# Power.net
KiCad netlist of a schematic drawn in Altium Designer
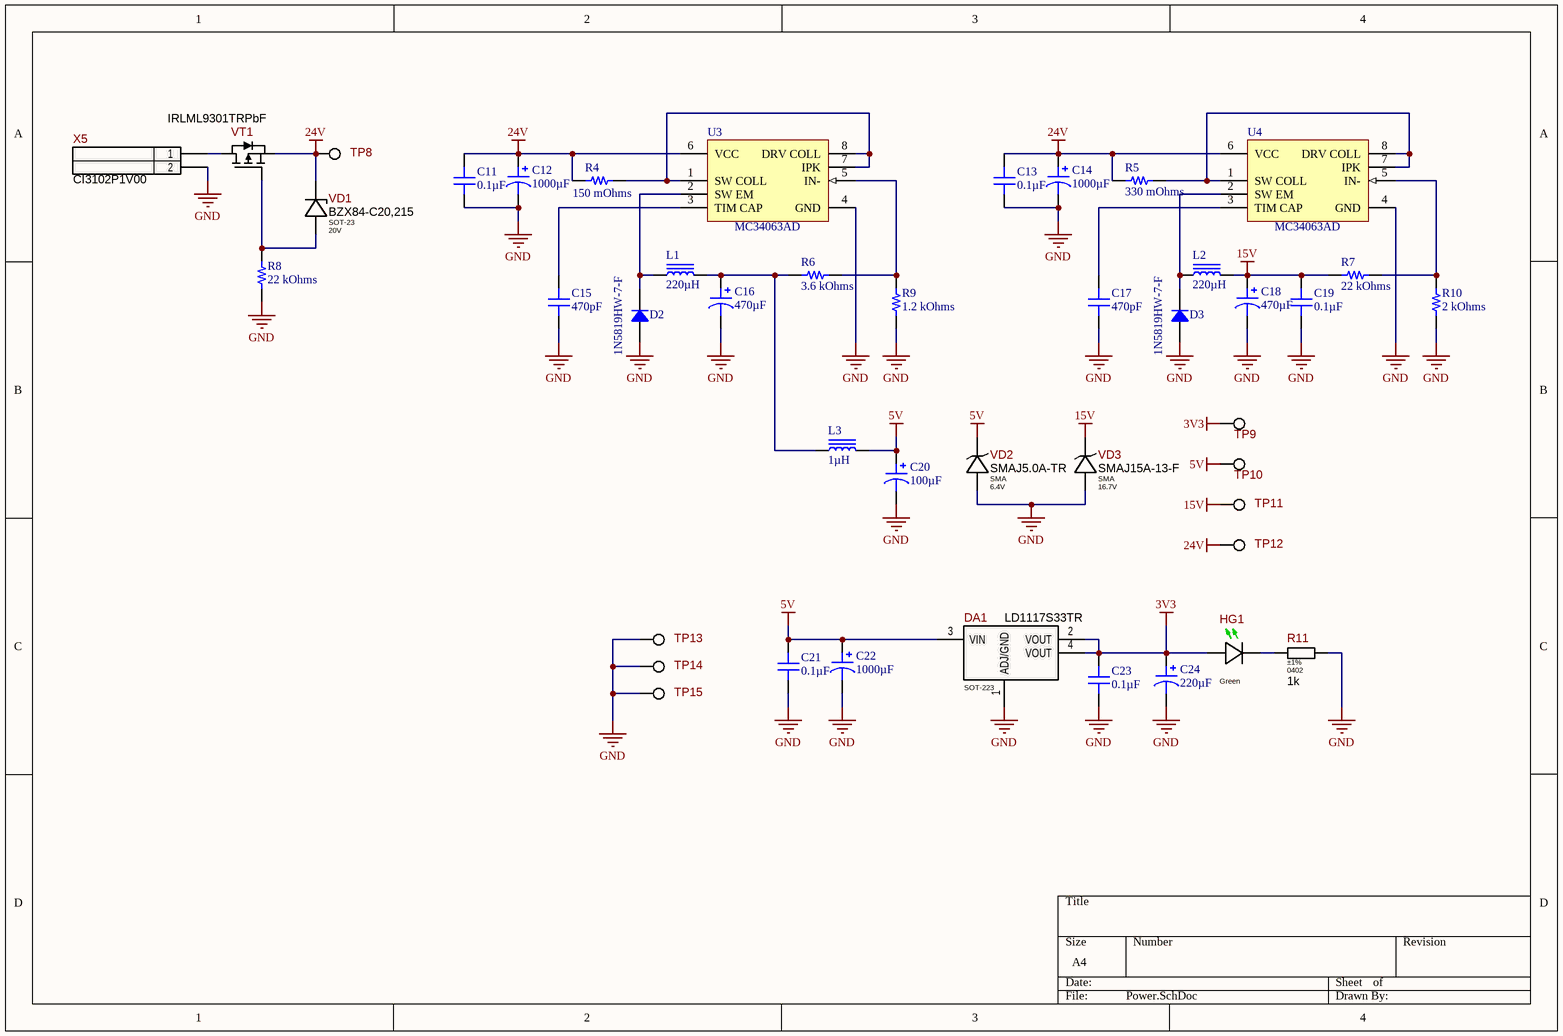
[diagram p0: Power.SchDoc]

(export (version "E")
  (design (tool "Eeschema 10.0.6"))
  (components
    (comp (ref "C11")
      (value "0.1µF")
      (footprint "CAP 0805_2012")
      (description "CAP CER 0.1UF 50V X7R 0805")
      (fields (field (name "PART NUMBER") "CC0805MRX7R9BB104") (field (name "MANUFACTURER") "Yageo"))
      (libsource (lib "Celestial Altium Library - altium_library") (part "Capacitor"))
    )
    (comp (ref "C12")
      (value "1000µF")
      (footprint "CAP TH ALUM ELEC D22.00mm S10.00mm H27.00mm")
      (description "CAP ALUM 1000UF 20% 35V SNAP IN")
      (fields (field (name "PART NUMBER") "LKG1V102MESZCK") (field (name "MANUFACTURER") "Nichicon"))
      (libsource (lib "Celestial Altium Library - altium_library") (part "Polarised Capacitor"))
    )
    (comp (ref "C13")
      (value "0.1µF")
      (footprint "CAP 0805_2012")
      (description "CAP CER 0.1UF 50V X7R 0805")
      (fields (field (name "PART NUMBER") "CC0805MRX7R9BB104") (field (name "MANUFACTURER") "Yageo"))
      (libsource (lib "Celestial Altium Library - altium_library") (part "Capacitor"))
    )
    (comp (ref "C14")
      (value "1000µF")
      (footprint "CAP TH ALUM ELEC D22.00mm S10.00mm H27.00mm")
      (description "CAP ALUM 1000UF 20% 35V SNAP IN")
      (fields (field (name "PART NUMBER") "LKG1V102MESZCK") (field (name "MANUFACTURER") "Nichicon"))
      (libsource (lib "Celestial Altium Library - altium_library") (part "Polarised Capacitor"))
    )
    (comp (ref "C15")
      (value "470pF")
      (footprint "CAP 0805_2012")
      (description "CAP CER 0805 470PF 50V ULTRA STA")
      (fields (field (name "PART NUMBER") "C0805X471J5HACAUTO") (field (name "MANUFACTURER") "KEMET"))
      (libsource (lib "Celestial Altium Library - altium_library") (part "Capacitor"))
    )
    (comp (ref "C16")
      (value "470µF")
      (footprint "CAP TH ALUM ELEC D8.00mm S3.50mm H12.50mm")
      (description "CAP ALUM 470UF 20% 10V RADIAL")
      (fields
        (field (name "PART NUMBER") "ECA-1AHG471")
        (field (name "MANUFACTURER") "Panasonic Electronic Components")
      )
      (libsource (lib "Celestial Altium Library - altium_library") (part "Polarised Capacitor"))
    )
    (comp (ref "C17")
      (value "470pF")
      (footprint "CAP 0805_2012")
      (description "CAP CER 0805 470PF 50V ULTRA STA")
      (fields (field (name "PART NUMBER") "C0805X471J5HACAUTO") (field (name "MANUFACTURER") "KEMET"))
      (libsource (lib "Celestial Altium Library - altium_library") (part "Capacitor"))
    )
    (comp (ref "C18")
      (value "470µF")
      (footprint "CAP TH ALUM ELEC D8.00mm S3.50mm H12.50mm")
      (description "CAP ALUM 470UF 20% 10V RADIAL")
      (fields
        (field (name "PART NUMBER") "ECA-1AHG471")
        (field (name "MANUFACTURER") "Panasonic Electronic Components")
      )
      (libsource (lib "Celestial Altium Library - altium_library") (part "Polarised Capacitor"))
    )
    (comp (ref "C19")
      (value "0.1µF")
      (footprint "CAP 0805_2012")
      (description "CAP CER 0.1UF 50V X7R 0805")
      (fields (field (name "PART NUMBER") "CC0805MRX7R9BB104") (field (name "MANUFACTURER") "Yageo"))
      (libsource (lib "Celestial Altium Library - altium_library") (part "Capacitor"))
    )
    (comp (ref "C20")
      (value "100µF")
      (footprint "CAP ALSMD 5.3MM H5.4MM")
      (description "CAP 100 UF 20% 6.3 V")
      (fields (field (name "PART NUMBER") "865090142005") (field (name "MANUFACTURER") "Würth Elektronik"))
      (libsource (lib "Celestial Altium Library - altium_library") (part "Polarised Capacitor"))
    )
    (comp (ref "C21")
      (value "0.1µF")
      (footprint "CAP 0805_2012")
      (description "CAP CER 0.1UF 50V X7R 0805")
      (fields (field (name "PART NUMBER") "CC0805MRX7R9BB104") (field (name "MANUFACTURER") "Yageo"))
      (libsource (lib "Celestial Altium Library - altium_library") (part "Capacitor"))
    )
    (comp (ref "C22")
      (value "1000µF")
      (footprint "CAP TH ALUM ELEC D22.00mm S10.00mm H27.00mm")
      (description "CAP ALUM 1000UF 20% 35V SNAP IN")
      (fields (field (name "PART NUMBER") "LKG1V102MESZCK") (field (name "MANUFACTURER") "Nichicon"))
      (libsource (lib "Celestial Altium Library - altium_library") (part "Polarised Capacitor"))
    )
    (comp (ref "C23")
      (value "0.1µF")
      (footprint "CAP 0805_2012")
      (description "CAP CER 0.1UF 50V X7R 0805")
      (fields (field (name "PART NUMBER") "CC0805MRX7R9BB104") (field (name "MANUFACTURER") "Yageo"))
      (libsource (lib "Celestial Altium Library - altium_library") (part "Capacitor"))
    )
    (comp (ref "C24")
      (value "220µF")
      (footprint "CAP ALSMD POLY 5.3MM H6.0MM")
      (description "CAP ALUM POLY 220UF 20% 6.3V SMD")
      (fields
        (field (name "PART NUMBER") "6SVPE220MW")
        (field (name "MANUFACTURER") "Panasonic Electronic Components")
      )
      (libsource (lib "Celestial Altium Library - altium_library") (part "Polarised Capacitor"))
    )
    (comp (ref "D2")
      (value "1N5819HW-7-F")
      (footprint "SOD-123")
      (description "DIODE SCHOTTKY 40V 1A SOD123")
      (fields (field (name "MANUFACTURER") "Diodes Incorporated"))
      (libsource (lib "Celestial Altium Library - altium_library") (part "Diode"))
    )
    (comp (ref "D3")
      (value "1N5819HW-7-F")
      (footprint "SOD-123")
      (description "DIODE SCHOTTKY 40V 1A SOD123")
      (fields (field (name "MANUFACTURER") "Diodes Incorporated"))
      (libsource (lib "Celestial Altium Library - altium_library") (part "Diode"))
    )
    (comp (ref "DA1")
      (value "LD1117S33TR")
      (footprint "SOT-223")
      (description "Adjustable and fixed low drop positive voltage regulator, 3.3V 800mA")
      (fields
        (field (name "PACKAGE") "SOT-223")
        (field (name "PART NUMBER") "LD1117S33TR")
        (field (name "MANUFACTURER") "STMicroelectronics")
      )
      (libsource (lib "SOG.T01.PWR.621.v1_1") (part "LD1117S33TR"))
    )
    (comp (ref "HG1")
      (value "19-21/GHC-YR1S2/3T")
      (footprint "LED-0603G-0.8mm")
      (description "Indication LED, Green 528nm, Clear, SMD 0603, Vf 2.7-3.7V, 112 - 285mcd @ 20mA, 110°")
      (fields (field (name "COLOR") "Green") (field (name "MANUFACTURER") "Everlight Electronics Co.,Ltd"))
      (libsource (lib "SOG.T01.PWR.621.v1_1") (part "19-21/GHC-YR1S2/3T"))
    )
    (comp (ref "L1")
      (value "220µH")
      (footprint "BOURNS SRR1280")
      (description "FIXED IND 220UH 1.6A 400MOHM SMD")
      (fields (field (name "PART NUMBER") "SRR1280-221K") (field (name "MANUFACTURER") "Bourns Inc."))
      (libsource (lib "Celestial Altium Library - altium_library") (part "Inductor"))
    )
    (comp (ref "L2")
      (value "220µH")
      (footprint "BOURNS SRR1280")
      (description "FIXED IND 220UH 1.6A 400MOHM SMD")
      (fields (field (name "PART NUMBER") "SRR1280-221K") (field (name "MANUFACTURER") "Bourns Inc."))
      (libsource (lib "Celestial Altium Library - altium_library") (part "Inductor"))
    )
    (comp (ref "L3")
      (value "1µH")
      (footprint "TAIYO YUDEN NRS5030")
      (description "FIXED IND 1UH 4A 19.5 MOHM SMD")
      (fields (field (name "PART NUMBER") "NRS5030T1R0NMGJV") (field (name "MANUFACTURER") "Taiyo Yuden"))
      (libsource (lib "Celestial Altium Library - altium_library") (part "Inductor"))
    )
    (comp (ref "R4")
      (value "150 mOhms")
      (footprint "RES 1206_3216")
      (description "RES 0.15 OHM 1% 1/4W 1206")
      (fields (field (name "PART NUMBER") "WSL1206R1500FEA") (field (name "MANUFACTURER") "Vishay Dale"))
      (libsource (lib "Celestial Altium Library - altium_library") (part "Resistor"))
    )
    (comp (ref "R5")
      (value "330 mOhms")
      (footprint "RES 1206_3216")
      (description "RES 0.33 OHM 1% 1/4W 1206")
      (fields
        (field (name "PART NUMBER") "ERJ-8RQFR33V")
        (field (name "MANUFACTURER") "Panasonic Electronic Components")
      )
      (libsource (lib "Celestial Altium Library - altium_library") (part "Resistor"))
    )
    (comp (ref "R6")
      (value "3.6 kOhms")
      (footprint "RES 0805_2012")
      (description "RES 3.6K OHM 1% 1/8W 0805")
      (fields
        (field (name "PART NUMBER") "RMCF0805FT3K60")
        (field (name "MANUFACTURER") "Stackpole Electronics Inc")
      )
      (libsource (lib "Celestial Altium Library - altium_library") (part "Resistor"))
    )
    (comp (ref "R7")
      (value "22 kOhms")
      (footprint "RES 0805_2012")
      (description "RES 22K OHM 0.5% 1/8W 0805")
      (fields
        (field (name "PART NUMBER") "ERA-6AED223V")
        (field (name "MANUFACTURER") "Panasonic Electronic Components")
      )
      (libsource (lib "Celestial Altium Library - altium_library") (part "Resistor"))
    )
    (comp (ref "R8")
      (value "22 kOhms")
      (footprint "RES 0805_2012")
      (description "RES 22K OHM 0.5% 1/8W 0805")
      (fields
        (field (name "PART NUMBER") "ERA-6AED223V")
        (field (name "MANUFACTURER") "Panasonic Electronic Components")
      )
      (libsource (lib "Celestial Altium Library - altium_library") (part "Resistor"))
    )
    (comp (ref "R9")
      (value "1.2 kOhms")
      (footprint "RES 0805_2012")
      (description "CRGP 0805 1K2 1%")
      (fields
        (field (name "PART NUMBER") "CRGP0805F1K2")
        (field (name "MANUFACTURER") "TE Connectivity Passive Product")
      )
      (libsource (lib "Celestial Altium Library - altium_library") (part "Resistor"))
    )
    (comp (ref "R10")
      (value "2 kOhms")
      (footprint "RES 0805_2012")
      (description "RES SMD 2K OHM 1% 0.4W 0805")
      (fields (field (name "PART NUMBER") "RCS08052K00FKEA") (field (name "MANUFACTURER") "Vishay Dale"))
      (libsource (lib "Celestial Altium Library - altium_library") (part "Resistor"))
    )
    (comp (ref "R11")
      (value "1k")
      (footprint "R_ANY_CHIP_0402_MED")
      (description "1 kOhms ±1% 1/16W 0402 Thick Film Resistor")
      (fields
        (field (name "TOLERANCE") "±1%")
        (field (name "PACKAGE") "0402")
        (field (name "PART NUMBER") "RC0402FR-071KL")
        (field (name "MANUFACTURER") "Yageo")
      )
      (libsource (lib "SOG.T01.PWR.621.v1_1") (part "RC0402FR-071KL"))
    )
    (comp (ref "TP8")
      (value "PAD-1.1mm")
      (footprint "PAD-1.1mm")
      (description "1.1mm Pad for Plug-In or Receptacle")
      (fields (field (name "MANUFACTURER") "NONE"))
      (libsource (lib "misc") (part "PAD-1.1mm"))
    )
    (comp (ref "TP9")
      (value "PAD-1.1mm")
      (footprint "PAD-1.1mm")
      (description "1.1mm Pad for Plug-In or Receptacle")
      (fields (field (name "MANUFACTURER") "NONE"))
      (libsource (lib "misc") (part "PAD-1.1mm"))
    )
    (comp (ref "TP10")
      (value "PAD-1.1mm")
      (footprint "PAD-1.1mm")
      (description "1.1mm Pad for Plug-In or Receptacle")
      (fields (field (name "MANUFACTURER") "NONE"))
      (libsource (lib "misc") (part "PAD-1.1mm"))
    )
    (comp (ref "TP11")
      (value "PAD-1.1mm")
      (footprint "PAD-1.1mm")
      (description "1.1mm Pad for Plug-In or Receptacle")
      (fields (field (name "MANUFACTURER") "NONE"))
      (libsource (lib "misc") (part "PAD-1.1mm"))
    )
    (comp (ref "TP12")
      (value "PAD-1.1mm")
      (footprint "PAD-1.1mm")
      (description "1.1mm Pad for Plug-In or Receptacle")
      (fields (field (name "MANUFACTURER") "NONE"))
      (libsource (lib "misc") (part "PAD-1.1mm"))
    )
    (comp (ref "TP13")
      (value "PAD-1.1mm")
      (footprint "PAD-1.1mm")
      (description "1.1mm Pad for Plug-In or Receptacle")
      (fields (field (name "MANUFACTURER") "NONE"))
      (libsource (lib "misc") (part "PAD-1.1mm"))
    )
    (comp (ref "TP14")
      (value "PAD-1.1mm")
      (footprint "PAD-1.1mm")
      (description "1.1mm Pad for Plug-In or Receptacle")
      (fields (field (name "MANUFACTURER") "NONE"))
      (libsource (lib "misc") (part "PAD-1.1mm"))
    )
    (comp (ref "TP15")
      (value "PAD-1.1mm")
      (footprint "PAD-1.1mm")
      (description "1.1mm Pad for Plug-In or Receptacle")
      (fields (field (name "MANUFACTURER") "NONE"))
      (libsource (lib "misc") (part "PAD-1.1mm"))
    )
    (comp (ref "U3")
      (value "MC34063AD")
      (footprint "751-05_N")
      (description "DC-to-DC Converter Control Circuit")
      (fields (field (name "PUBLISHER") "Altium Limited"))
      (libsource (lib "ON Semi Power Mgt DC-DC Converter") (part "MC34063AD"))
    )
    (comp (ref "U4")
      (value "MC34063AD")
      (footprint "751-05_N")
      (description "DC-to-DC Converter Control Circuit")
      (fields (field (name "PUBLISHER") "Altium Limited"))
      (libsource (lib "ON Semi Power Mgt DC-DC Converter") (part "MC34063AD"))
    )
    (comp (ref "VD1")
      (value "BZX84-C20,215")
      (footprint "SOT-23_MED")
      (description "Zener Diode 20V, 250mW, ±5%, SOT-23")
      (fields
        (field (name "PART NUMBER") "BZX84-C20,215")
        (field (name "PACKAGE") "SOT-23")
        (field (name "VOLTAGE") "20V")
        (field (name "MANUFACTURER") "Nexperia USA Inc.")
      )
      (libsource (lib "Diodes") (part "BZX84-C20,215"))
    )
    (comp (ref "VD2")
      (value "SMAJ5.0A")
      (footprint "SMA_MED")
      (description "TVS Diode 13.4V Clamp, 174A (8/20µs) Ipp, SMA")
      (fields
        (field (name "PART NUMBER") "SMAJ5.0A-TR")
        (field (name "PACKAGE") "SMA")
        (field (name "VOLTAGE") "6.4V")
        (field (name "MANUFACTURER") "STMicroelectronics")
      )
      (libsource (lib "Diodes") (part "SMAJ5.0A-TR"))
    )
    (comp (ref "VD3")
      (value "SMAJ15A")
      (footprint "SMA_MED")
      (description "TVS Diode 24.4V Clamp, 16.4A (10/1000 µs) Ipp, SMA")
      (fields
        (field (name "PART NUMBER") "SMAJ15A-13-F")
        (field (name "PACKAGE") "SMA")
        (field (name "VOLTAGE") "16.7V")
        (field (name "MANUFACTURER") "Diodes Incorporated")
      )
      (libsource (lib "Diodes") (part "SMAJ15A-13-F"))
    )
    (comp (ref "VT1")
      (value "IRLML9301TRPbF")
      (footprint "SOT-23_MED")
      (description "-30V, -3.6A max P-Channel HEXFET MOSFET, 82mOhm @ Vgs = -4.5V")
      (fields
        (field (name "PART NUMBER") "IRLML9301TRPbF")
        (field (name "MANUFACTURER") "Infineon Technologies")
      )
      (libsource (lib "Transistors") (part "IRLML9301TRPbF"))
    )
    (comp (ref "X5")
      (value "WH-02S")
      (footprint "WF-2S")
      (description "WH Series 2.54mm Wire to Board Straight DIP Type Headers, 2-Pin")
      (fields (field (name "PART NUMBER") "CI3102P1V00") (field (name "MANUFACTURER") "CviLux"))
      (libsource (lib "SOG.T01.PWR.621.v1_1") (part "CI3102P1V00"))
    )
  )
  (nets
    (net (code "1") (name "3V3") (class "Default")
      (node (ref "C23") (pin "2") (pinfunction "2_2") (pintype "passive"))
      (node (ref "C24") (pin "1") (pinfunction "1_1") (pintype "passive"))
      (node (ref "DA1") (pin "2") (pinfunction "VOUT_2") (pintype "passive"))
      (node (ref "DA1") (pin "4") (pinfunction "VOUT_4") (pintype "passive"))
      (node (ref "HG1") (pin "AN") (pinfunction "Anode_AN") (pintype "passive"))
      (node (ref "TP9") (pin "1") (pintype "passive"))
    )
    (net (code "2") (name "5V") (class "Default")
      (node (ref "C20") (pin "1") (pinfunction "1_1") (pintype "passive"))
      (node (ref "C21") (pin "2") (pinfunction "2_2") (pintype "passive"))
      (node (ref "C22") (pin "1") (pinfunction "1_1") (pintype "passive"))
      (node (ref "DA1") (pin "3") (pinfunction "VIN_3") (pintype "passive"))
      (node (ref "L3") (pin "2") (pinfunction "2_2") (pintype "passive"))
      (node (ref "TP10") (pin "1") (pintype "passive"))
      (node (ref "VD2") (pin "CA") (pintype "passive"))
    )
    (net (code "3") (name "15V") (class "Default")
      (node (ref "C18") (pin "1") (pinfunction "1_1") (pintype "passive"))
      (node (ref "C19") (pin "2") (pinfunction "2_2") (pintype "passive"))
      (node (ref "L2") (pin "2") (pinfunction "2_2") (pintype "passive"))
      (node (ref "R7") (pin "1") (pinfunction "1_1") (pintype "passive"))
      (node (ref "TP11") (pin "1") (pintype "passive"))
      (node (ref "VD3") (pin "CA") (pintype "passive"))
    )
    (net (code "4") (name "24V") (class "Default")
      (node (ref "C11") (pin "2") (pinfunction "2_2") (pintype "passive"))
      (node (ref "C12") (pin "1") (pinfunction "1_1") (pintype "passive"))
      (node (ref "C13") (pin "2") (pinfunction "2_2") (pintype "passive"))
      (node (ref "C14") (pin "1") (pinfunction "1_1") (pintype "passive"))
      (node (ref "R4") (pin "1") (pinfunction "1_1") (pintype "passive"))
      (node (ref "R5") (pin "1") (pinfunction "1_1") (pintype "passive"))
      (node (ref "TP12") (pin "1") (pintype "passive"))
      (node (ref "TP8") (pin "1") (pintype "passive"))
      (node (ref "U3") (pin "6") (pinfunction "VCC_6") (pintype "power_in"))
      (node (ref "U4") (pin "6") (pinfunction "VCC_6") (pintype "power_in"))
      (node (ref "VD1") (pin "3") (pinfunction "Cathode_3") (pintype "passive"))
      (node (ref "VT1") (pin "2") (pinfunction "S_2") (pintype "passive"))
    )
    (net (code "5") (name "GND") (class "Default")
      (node (ref "C11") (pin "1") (pinfunction "1_1") (pintype "passive"))
      (node (ref "C12") (pin "2") (pinfunction "2_2") (pintype "passive"))
      (node (ref "C13") (pin "1") (pinfunction "1_1") (pintype "passive"))
      (node (ref "C14") (pin "2") (pinfunction "2_2") (pintype "passive"))
      (node (ref "C15") (pin "1") (pinfunction "1_1") (pintype "passive"))
      (node (ref "C16") (pin "2") (pinfunction "2_2") (pintype "passive"))
      (node (ref "C17") (pin "1") (pinfunction "1_1") (pintype "passive"))
      (node (ref "C18") (pin "2") (pinfunction "2_2") (pintype "passive"))
      (node (ref "C19") (pin "1") (pinfunction "1_1") (pintype "passive"))
      (node (ref "C20") (pin "2") (pinfunction "2_2") (pintype "passive"))
      (node (ref "C21") (pin "1") (pinfunction "1_1") (pintype "passive"))
      (node (ref "C22") (pin "2") (pinfunction "2_2") (pintype "passive"))
      (node (ref "C23") (pin "1") (pinfunction "1_1") (pintype "passive"))
      (node (ref "C24") (pin "2") (pinfunction "2_2") (pintype "passive"))
      (node (ref "D2") (pin "1") (pinfunction "1_1") (pintype "passive"))
      (node (ref "D3") (pin "1") (pinfunction "1_1") (pintype "passive"))
      (node (ref "DA1") (pin "1") (pinfunction "ADJ/GND_1") (pintype "passive"))
      (node (ref "R10") (pin "1") (pinfunction "1_1") (pintype "passive"))
      (node (ref "R11") (pin "2") (pintype "passive"))
      (node (ref "R8") (pin "1") (pinfunction "1_1") (pintype "passive"))
      (node (ref "R9") (pin "1") (pinfunction "1_1") (pintype "passive"))
      (node (ref "TP13") (pin "1") (pintype "passive"))
      (node (ref "TP14") (pin "1") (pintype "passive"))
      (node (ref "TP15") (pin "1") (pintype "passive"))
      (node (ref "U3") (pin "4") (pinfunction "GND_4") (pintype "power_in"))
      (node (ref "U4") (pin "4") (pinfunction "GND_4") (pintype "power_in"))
      (node (ref "VD2") (pin "AN") (pintype "passive"))
      (node (ref "VD3") (pin "AN") (pintype "passive"))
      (node (ref "X5") (pin "2") (pinfunction "2_2") (pintype "passive"))
    )
    (net (code "6") (name "Net-(C16-Pad1)") (class "Default")
      (node (ref "C16") (pin "1") (pinfunction "1_1") (pintype "passive"))
      (node (ref "L1") (pin "2") (pinfunction "2_2") (pintype "passive"))
      (node (ref "L3") (pin "1") (pinfunction "1_1") (pintype "passive"))
      (node (ref "R6") (pin "1") (pinfunction "1_1") (pintype "passive"))
    )
    (net (code "7") (name "Net-(HG1-Cathode)") (class "Default")
      (node (ref "HG1") (pin "CA") (pinfunction "Cathode_CA") (pintype "passive"))
      (node (ref "R11") (pin "1") (pintype "passive"))
    )
    (net (code "8") (name "Net-(U3-DRV_COLL)") (class "Default")
      (node (ref "R4") (pin "2") (pinfunction "2_2") (pintype "passive"))
      (node (ref "U3") (pin "1") (pinfunction "SW_COLL_1") (pintype "passive"))
      (node (ref "U3") (pin "7") (pinfunction "IPK_7") (pintype "passive"))
      (node (ref "U3") (pin "8") (pinfunction "DRV_COLL_8") (pintype "open_collector"))
    )
    (net (code "9") (name "Net-(U3-IN-)") (class "Default")
      (node (ref "R6") (pin "2") (pinfunction "2_2") (pintype "passive"))
      (node (ref "R9") (pin "2") (pinfunction "2_2") (pintype "passive"))
      (node (ref "U3") (pin "5") (pinfunction "IN-_5") (pintype "input"))
    )
    (net (code "10") (name "Net-(U3-SW_EM)") (class "Default")
      (node (ref "D2") (pin "2") (pinfunction "2_2") (pintype "passive"))
      (node (ref "L1") (pin "1") (pinfunction "1_1") (pintype "passive"))
      (node (ref "U3") (pin "2") (pinfunction "SW_EM_2") (pintype "passive"))
    )
    (net (code "11") (name "Net-(U3-TIM_CAP)") (class "Default")
      (node (ref "C15") (pin "2") (pinfunction "2_2") (pintype "passive"))
      (node (ref "U3") (pin "3") (pinfunction "TIM_CAP_3") (pintype "passive"))
    )
    (net (code "12") (name "Net-(U4-DRV_COLL)") (class "Default")
      (node (ref "R5") (pin "2") (pinfunction "2_2") (pintype "passive"))
      (node (ref "U4") (pin "1") (pinfunction "SW_COLL_1") (pintype "passive"))
      (node (ref "U4") (pin "7") (pinfunction "IPK_7") (pintype "passive"))
      (node (ref "U4") (pin "8") (pinfunction "DRV_COLL_8") (pintype "open_collector"))
    )
    (net (code "13") (name "Net-(U4-IN-)") (class "Default")
      (node (ref "R10") (pin "2") (pinfunction "2_2") (pintype "passive"))
      (node (ref "R7") (pin "2") (pinfunction "2_2") (pintype "passive"))
      (node (ref "U4") (pin "5") (pinfunction "IN-_5") (pintype "input"))
    )
    (net (code "14") (name "Net-(U4-SW_EM)") (class "Default")
      (node (ref "D3") (pin "2") (pinfunction "2_2") (pintype "passive"))
      (node (ref "L2") (pin "1") (pinfunction "1_1") (pintype "passive"))
      (node (ref "U4") (pin "2") (pinfunction "SW_EM_2") (pintype "passive"))
    )
    (net (code "15") (name "Net-(U4-TIM_CAP)") (class "Default")
      (node (ref "C17") (pin "2") (pinfunction "2_2") (pintype "passive"))
      (node (ref "U4") (pin "3") (pinfunction "TIM_CAP_3") (pintype "passive"))
    )
    (net (code "16") (name "Net-(VD1-Anode)") (class "Default")
      (node (ref "R8") (pin "2") (pinfunction "2_2") (pintype "passive"))
      (node (ref "VD1") (pin "1") (pinfunction "Anode_1") (pintype "passive"))
      (node (ref "VT1") (pin "1") (pinfunction "G_1") (pintype "passive"))
    )
    (net (code "17") (name "Net-(VT1-D)") (class "Default")
      (node (ref "VT1") (pin "3") (pinfunction "D_3") (pintype "passive"))
      (node (ref "X5") (pin "1") (pinfunction "1_1") (pintype "passive"))
    )
    (net (code "18") (name "unconnected-(VD1-NC-Pad2)") (class "Default")
      (node (ref "VD1") (pin "2") (pinfunction "NC_2") (pintype "passive"))
    )
  )
)
